# TOP.net
KiCad netlist of a schematic drawn in Altium Designer
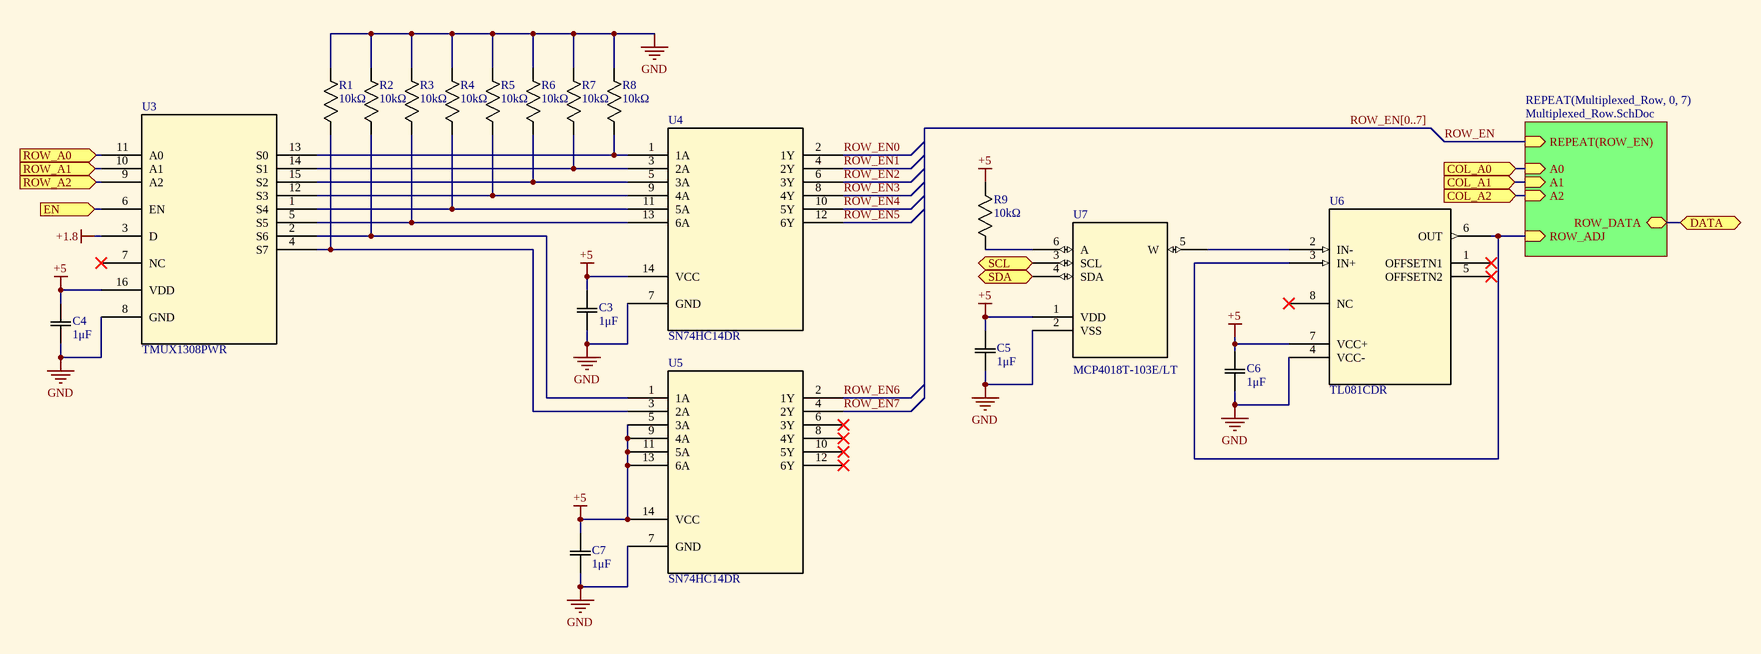
[diagram p0: TOP.SchDoc]

(export (version "E")
  (design (tool "Eeschema 10.0.6"))
  (components
    (comp (ref "C3")
      (value "1μF")
      (footprint "CAP_CL10_SAM")
      (description "No Description Available")
      (libsource (lib "Component_Schematics") (part "CL10B104KB8NNWC"))
    )
    (comp (ref "C4")
      (value "1μF")
      (footprint "CAP_CL10_SAM")
      (description "No Description Available")
      (libsource (lib "Component_Schematics") (part "CL10B104KB8NNWC"))
    )
    (comp (ref "C5")
      (value "1μF")
      (footprint "CAP_CL10_SAM")
      (description "No Description Available")
      (libsource (lib "Component_Schematics") (part "CL10B104KB8NNWC"))
    )
    (comp (ref "C6")
      (value "1μF")
      (footprint "CAP_CL10_SAM")
      (description "No Description Available")
      (libsource (lib "Component_Schematics") (part "CL10B104KB8NNWC"))
    )
    (comp (ref "C7")
      (value "1μF")
      (footprint "CAP_CL10_SAM")
      (description "No Description Available")
      (libsource (lib "Component_Schematics") (part "CL10B104KB8NNWC"))
    )
    (comp (ref "R1")
      (value "10kΩ")
      (footprint "RES_RC0603_YAG")
      (description "No Description Available")
      (fields
        (field (name "MANUFACTURER_PART_NUMBER") "RC0603FR-7W10KL")
        (field (name "COPYRIGHT") "Copyright (C) 2023 Ultra Librarian. All rights reserved.")
      )
      (libsource (lib "Component_Schematics") (part "RC0603FR-7W10KL"))
    )
    (comp (ref "R2")
      (value "10kΩ")
      (footprint "RES_RC0603_YAG")
      (description "No Description Available")
      (fields
        (field (name "MANUFACTURER_PART_NUMBER") "RC0603FR-7W10KL")
        (field (name "COPYRIGHT") "Copyright (C) 2023 Ultra Librarian. All rights reserved.")
      )
      (libsource (lib "Component_Schematics") (part "RC0603FR-7W10KL"))
    )
    (comp (ref "R3")
      (value "10kΩ")
      (footprint "RES_RC0603_YAG")
      (description "No Description Available")
      (fields
        (field (name "MANUFACTURER_PART_NUMBER") "RC0603FR-7W10KL")
        (field (name "COPYRIGHT") "Copyright (C) 2023 Ultra Librarian. All rights reserved.")
      )
      (libsource (lib "Component_Schematics") (part "RC0603FR-7W10KL"))
    )
    (comp (ref "R4")
      (value "10kΩ")
      (footprint "RES_RC0603_YAG")
      (description "No Description Available")
      (fields
        (field (name "MANUFACTURER_PART_NUMBER") "RC0603FR-7W10KL")
        (field (name "COPYRIGHT") "Copyright (C) 2023 Ultra Librarian. All rights reserved.")
      )
      (libsource (lib "Component_Schematics") (part "RC0603FR-7W10KL"))
    )
    (comp (ref "R5")
      (value "10kΩ")
      (footprint "RES_RC0603_YAG")
      (description "No Description Available")
      (fields
        (field (name "MANUFACTURER_PART_NUMBER") "RC0603FR-7W10KL")
        (field (name "COPYRIGHT") "Copyright (C) 2023 Ultra Librarian. All rights reserved.")
      )
      (libsource (lib "Component_Schematics") (part "RC0603FR-7W10KL"))
    )
    (comp (ref "R6")
      (value "10kΩ")
      (footprint "RES_RC0603_YAG")
      (description "No Description Available")
      (fields
        (field (name "MANUFACTURER_PART_NUMBER") "RC0603FR-7W10KL")
        (field (name "COPYRIGHT") "Copyright (C) 2023 Ultra Librarian. All rights reserved.")
      )
      (libsource (lib "Component_Schematics") (part "RC0603FR-7W10KL"))
    )
    (comp (ref "R7")
      (value "10kΩ")
      (footprint "RES_RC0603_YAG")
      (description "No Description Available")
      (fields
        (field (name "MANUFACTURER_PART_NUMBER") "RC0603FR-7W10KL")
        (field (name "COPYRIGHT") "Copyright (C) 2023 Ultra Librarian. All rights reserved.")
      )
      (libsource (lib "Component_Schematics") (part "RC0603FR-7W10KL"))
    )
    (comp (ref "R8")
      (value "10kΩ")
      (footprint "RES_RC0603_YAG")
      (description "No Description Available")
      (fields
        (field (name "MANUFACTURER_PART_NUMBER") "RC0603FR-7W10KL")
        (field (name "COPYRIGHT") "Copyright (C) 2023 Ultra Librarian. All rights reserved.")
      )
      (libsource (lib "Component_Schematics") (part "RC0603FR-7W10KL"))
    )
    (comp (ref "R9")
      (value "10kΩ")
      (footprint "RES_RC0603_YAG")
      (description "No Description Available")
      (fields
        (field (name "MANUFACTURER_PART_NUMBER") "RC0603FR-7W10KL")
        (field (name "COPYRIGHT") "Copyright (C) 2023 Ultra Librarian. All rights reserved.")
      )
      (libsource (lib "Component_Schematics") (part "RC0603FR-7W10KL"))
    )
    (comp (ref "U3")
      (value "TMUX1308PWR")
      (footprint "TSSOP16_PW_TEX")
      (description "No Description Available")
      (libsource (lib "Component_Schematics") (part "TMUX1308PWR"))
    )
    (comp (ref "U4")
      (value "SN74HC14DR")
      (footprint "D14")
      (description "No Description Available")
      (libsource (lib "Component_Schematics") (part "SN74HC14DR"))
    )
    (comp (ref "U5")
      (value "SN74HC14DR")
      (footprint "D14")
      (description "No Description Available")
      (libsource (lib "Component_Schematics") (part "SN74HC14DR"))
    )
    (comp (ref "U6")
      (value "TL081CDR")
      (footprint "D8")
      (description "No Description Available")
      (fields (field (name "COPYRIGHT") "Copyright (C) 2023 Ultra Librarian. All rights reserved."))
      (libsource (lib "Component_Schematics") (part "TL081CDR"))
    )
    (comp (ref "U7")
      (value "MCP4018T-103E/LT")
      (footprint "SC70-6_MC_MCH")
      (description "No Description Available")
      (fields (field (name "COPYRIGHT") "Copyright (C) 2023 Ultra Librarian. All rights reserved."))
      (libsource (lib "Component_Schematics") (part "MCP4018T-103ELT"))
    )
  )
  (nets
    (net (code "1") (name "+1.8") (class "Default")
      (node (ref "U3") (pin "3") (pinfunction "D_3") (pintype "passive"))
    )
    (net (code "2") (name "+5") (class "Default")
      (node (ref "C3") (pin "2") (pinfunction "2_2") (pintype "passive"))
      (node (ref "C4") (pin "2") (pinfunction "2_2") (pintype "passive"))
      (node (ref "C5") (pin "2") (pinfunction "2_2") (pintype "passive"))
      (node (ref "C6") (pin "2") (pinfunction "2_2") (pintype "passive"))
      (node (ref "C7") (pin "2") (pinfunction "2_2") (pintype "passive"))
      (node (ref "R9") (pin "2") (pinfunction "2_2") (pintype "passive"))
      (node (ref "U3") (pin "16") (pinfunction "VDD_16") (pintype "power_in"))
      (node (ref "U4") (pin "14") (pinfunction "VCC_14") (pintype "power_in"))
      (node (ref "U5") (pin "11") (pinfunction "5A_11") (pintype "passive"))
      (node (ref "U5") (pin "13") (pinfunction "6A_13") (pintype "passive"))
      (node (ref "U5") (pin "14") (pinfunction "VCC_14") (pintype "power_in"))
      (node (ref "U5") (pin "5") (pinfunction "3A_5") (pintype "passive"))
      (node (ref "U5") (pin "9") (pinfunction "4A_9") (pintype "passive"))
      (node (ref "U6") (pin "7") (pinfunction "VCC+_7") (pintype "power_in"))
      (node (ref "U7") (pin "1") (pinfunction "VDD_1") (pintype "power_in"))
    )
    (net (code "7") (name "/EN") (class "Default")
      (node (ref "U3") (pin "6") (pinfunction "EN_6") (pintype "passive"))
    )
    (net (code "8") (name "/ROW_A0") (class "Default")
      (node (ref "U3") (pin "11") (pinfunction "A0_11") (pintype "passive"))
    )
    (net (code "9") (name "/ROW_A1") (class "Default")
      (node (ref "U3") (pin "10") (pinfunction "A1_10") (pintype "passive"))
    )
    (net (code "10") (name "/ROW_A2") (class "Default")
      (node (ref "U3") (pin "9") (pinfunction "A2_9") (pintype "passive"))
    )
    (net (code "11") (name "/ROW_ADJ") (class "Default")
      (node (ref "U6") (pin "3") (pinfunction "IN+_3") (pintype "input"))
      (node (ref "U6") (pin "6") (pinfunction "OUT_6") (pintype "output"))
    )
    (net (code "13") (name "/ROW_EN0") (class "Default")
      (node (ref "U4") (pin "2") (pinfunction "1Y_2") (pintype "passive"))
    )
    (net (code "14") (name "/ROW_EN1") (class "Default")
      (node (ref "U4") (pin "4") (pinfunction "2Y_4") (pintype "passive"))
    )
    (net (code "15") (name "/ROW_EN2") (class "Default")
      (node (ref "U4") (pin "6") (pinfunction "3Y_6") (pintype "passive"))
    )
    (net (code "16") (name "/ROW_EN3") (class "Default")
      (node (ref "U4") (pin "8") (pinfunction "4Y_8") (pintype "passive"))
    )
    (net (code "17") (name "/ROW_EN4") (class "Default")
      (node (ref "U4") (pin "10") (pinfunction "5Y_10") (pintype "passive"))
    )
    (net (code "18") (name "/ROW_EN5") (class "Default")
      (node (ref "U4") (pin "12") (pinfunction "6Y_12") (pintype "passive"))
    )
    (net (code "19") (name "/ROW_EN6") (class "Default")
      (node (ref "U5") (pin "2") (pinfunction "1Y_2") (pintype "passive"))
    )
    (net (code "20") (name "/ROW_EN7") (class "Default")
      (node (ref "U5") (pin "4") (pinfunction "2Y_4") (pintype "passive"))
    )
    (net (code "22") (name "/SCL") (class "Default")
      (node (ref "U7") (pin "3") (pinfunction "SCL_3") (pintype "bidirectional"))
    )
    (net (code "23") (name "/SDA") (class "Default")
      (node (ref "U7") (pin "4") (pinfunction "SDA_4") (pintype "bidirectional"))
    )
    (net (code "24") (name "GND") (class "Default")
      (node (ref "C3") (pin "1") (pinfunction "1_1") (pintype "passive"))
      (node (ref "C4") (pin "1") (pinfunction "1_1") (pintype "passive"))
      (node (ref "C5") (pin "1") (pinfunction "1_1") (pintype "passive"))
      (node (ref "C6") (pin "1") (pinfunction "1_1") (pintype "passive"))
      (node (ref "C7") (pin "1") (pinfunction "1_1") (pintype "passive"))
      (node (ref "R1") (pin "2") (pinfunction "2_2") (pintype "passive"))
      (node (ref "R2") (pin "2") (pinfunction "2_2") (pintype "passive"))
      (node (ref "R3") (pin "2") (pinfunction "2_2") (pintype "passive"))
      (node (ref "R4") (pin "2") (pinfunction "2_2") (pintype "passive"))
      (node (ref "R5") (pin "2") (pinfunction "2_2") (pintype "passive"))
      (node (ref "R6") (pin "2") (pinfunction "2_2") (pintype "passive"))
      (node (ref "R7") (pin "2") (pinfunction "2_2") (pintype "passive"))
      (node (ref "R8") (pin "2") (pinfunction "2_2") (pintype "passive"))
      (node (ref "U3") (pin "8") (pinfunction "GND_8") (pintype "power_in"))
      (node (ref "U4") (pin "7") (pinfunction "GND_7") (pintype "power_in"))
      (node (ref "U5") (pin "7") (pinfunction "GND_7") (pintype "power_in"))
      (node (ref "U6") (pin "4") (pinfunction "VCC-_4") (pintype "power_in"))
      (node (ref "U7") (pin "2") (pinfunction "VSS_2") (pintype "power_in"))
    )
    (net (code "25") (name "Net-(U3-S0)") (class "Default")
      (node (ref "R8") (pin "1") (pinfunction "1_1") (pintype "passive"))
      (node (ref "U3") (pin "13") (pinfunction "S0_13") (pintype "passive"))
      (node (ref "U4") (pin "1") (pinfunction "1A_1") (pintype "passive"))
    )
    (net (code "26") (name "Net-(U3-S1)") (class "Default")
      (node (ref "R7") (pin "1") (pinfunction "1_1") (pintype "passive"))
      (node (ref "U3") (pin "14") (pinfunction "S1_14") (pintype "passive"))
      (node (ref "U4") (pin "3") (pinfunction "2A_3") (pintype "passive"))
    )
    (net (code "27") (name "Net-(U3-S2)") (class "Default")
      (node (ref "R6") (pin "1") (pinfunction "1_1") (pintype "passive"))
      (node (ref "U3") (pin "15") (pinfunction "S2_15") (pintype "passive"))
      (node (ref "U4") (pin "5") (pinfunction "3A_5") (pintype "passive"))
    )
    (net (code "28") (name "Net-(U3-S3)") (class "Default")
      (node (ref "R5") (pin "1") (pinfunction "1_1") (pintype "passive"))
      (node (ref "U3") (pin "12") (pinfunction "S3_12") (pintype "passive"))
      (node (ref "U4") (pin "9") (pinfunction "4A_9") (pintype "passive"))
    )
    (net (code "29") (name "Net-(U3-S4)") (class "Default")
      (node (ref "R4") (pin "1") (pinfunction "1_1") (pintype "passive"))
      (node (ref "U3") (pin "1") (pinfunction "S4_1") (pintype "passive"))
      (node (ref "U4") (pin "11") (pinfunction "5A_11") (pintype "passive"))
    )
    (net (code "30") (name "Net-(U3-S5)") (class "Default")
      (node (ref "R3") (pin "1") (pinfunction "1_1") (pintype "passive"))
      (node (ref "U3") (pin "5") (pinfunction "S5_5") (pintype "passive"))
      (node (ref "U4") (pin "13") (pinfunction "6A_13") (pintype "passive"))
    )
    (net (code "31") (name "Net-(U3-S6)") (class "Default")
      (node (ref "R2") (pin "1") (pinfunction "1_1") (pintype "passive"))
      (node (ref "U3") (pin "2") (pinfunction "S6_2") (pintype "passive"))
      (node (ref "U5") (pin "1") (pinfunction "1A_1") (pintype "passive"))
    )
    (net (code "32") (name "Net-(U3-S7)") (class "Default")
      (node (ref "R1") (pin "1") (pinfunction "1_1") (pintype "passive"))
      (node (ref "U3") (pin "4") (pinfunction "S7_4") (pintype "passive"))
      (node (ref "U5") (pin "3") (pinfunction "2A_3") (pintype "passive"))
    )
    (net (code "33") (name "Net-(U6-IN-)") (class "Default")
      (node (ref "U6") (pin "2") (pinfunction "IN-_2") (pintype "input"))
      (node (ref "U7") (pin "5") (pinfunction "W_5") (pintype "bidirectional"))
    )
    (net (code "34") (name "Net-(U7-A)") (class "Default")
      (node (ref "R9") (pin "1") (pinfunction "1_1") (pintype "passive"))
      (node (ref "U7") (pin "6") (pinfunction "A_6") (pintype "bidirectional"))
    )
    (net (code "35") (name "unconnected-(U3-NC-Pad7)") (class "Default")
      (node (ref "U3") (pin "7") (pinfunction "NC_7") (pintype "passive+no_connect"))
    )
    (net (code "36") (name "unconnected-(U5-3Y-Pad6)") (class "Default")
      (node (ref "U5") (pin "6") (pinfunction "3Y_6") (pintype "passive+no_connect"))
    )
    (net (code "37") (name "unconnected-(U5-4Y-Pad8)") (class "Default")
      (node (ref "U5") (pin "8") (pinfunction "4Y_8") (pintype "passive+no_connect"))
    )
    (net (code "38") (name "unconnected-(U5-5Y-Pad10)") (class "Default")
      (node (ref "U5") (pin "10") (pinfunction "5Y_10") (pintype "passive+no_connect"))
    )
    (net (code "39") (name "unconnected-(U5-6Y-Pad12)") (class "Default")
      (node (ref "U5") (pin "12") (pinfunction "6Y_12") (pintype "passive+no_connect"))
    )
    (net (code "40") (name "unconnected-(U6-NC-Pad8)") (class "Default")
      (node (ref "U6") (pin "8") (pinfunction "NC_8") (pintype "passive+no_connect"))
    )
    (net (code "41") (name "unconnected-(U6-OFFSETN1-Pad1)") (class "Default")
      (node (ref "U6") (pin "1") (pinfunction "OFFSETN1_1") (pintype "passive+no_connect"))
    )
    (net (code "42") (name "unconnected-(U6-OFFSETN2-Pad5)") (class "Default")
      (node (ref "U6") (pin "5") (pinfunction "OFFSETN2_5") (pintype "passive+no_connect"))
    )
  )
)
